# IMX385_PINOUT.net
KiCad netlist of a schematic drawn in Altium Designer
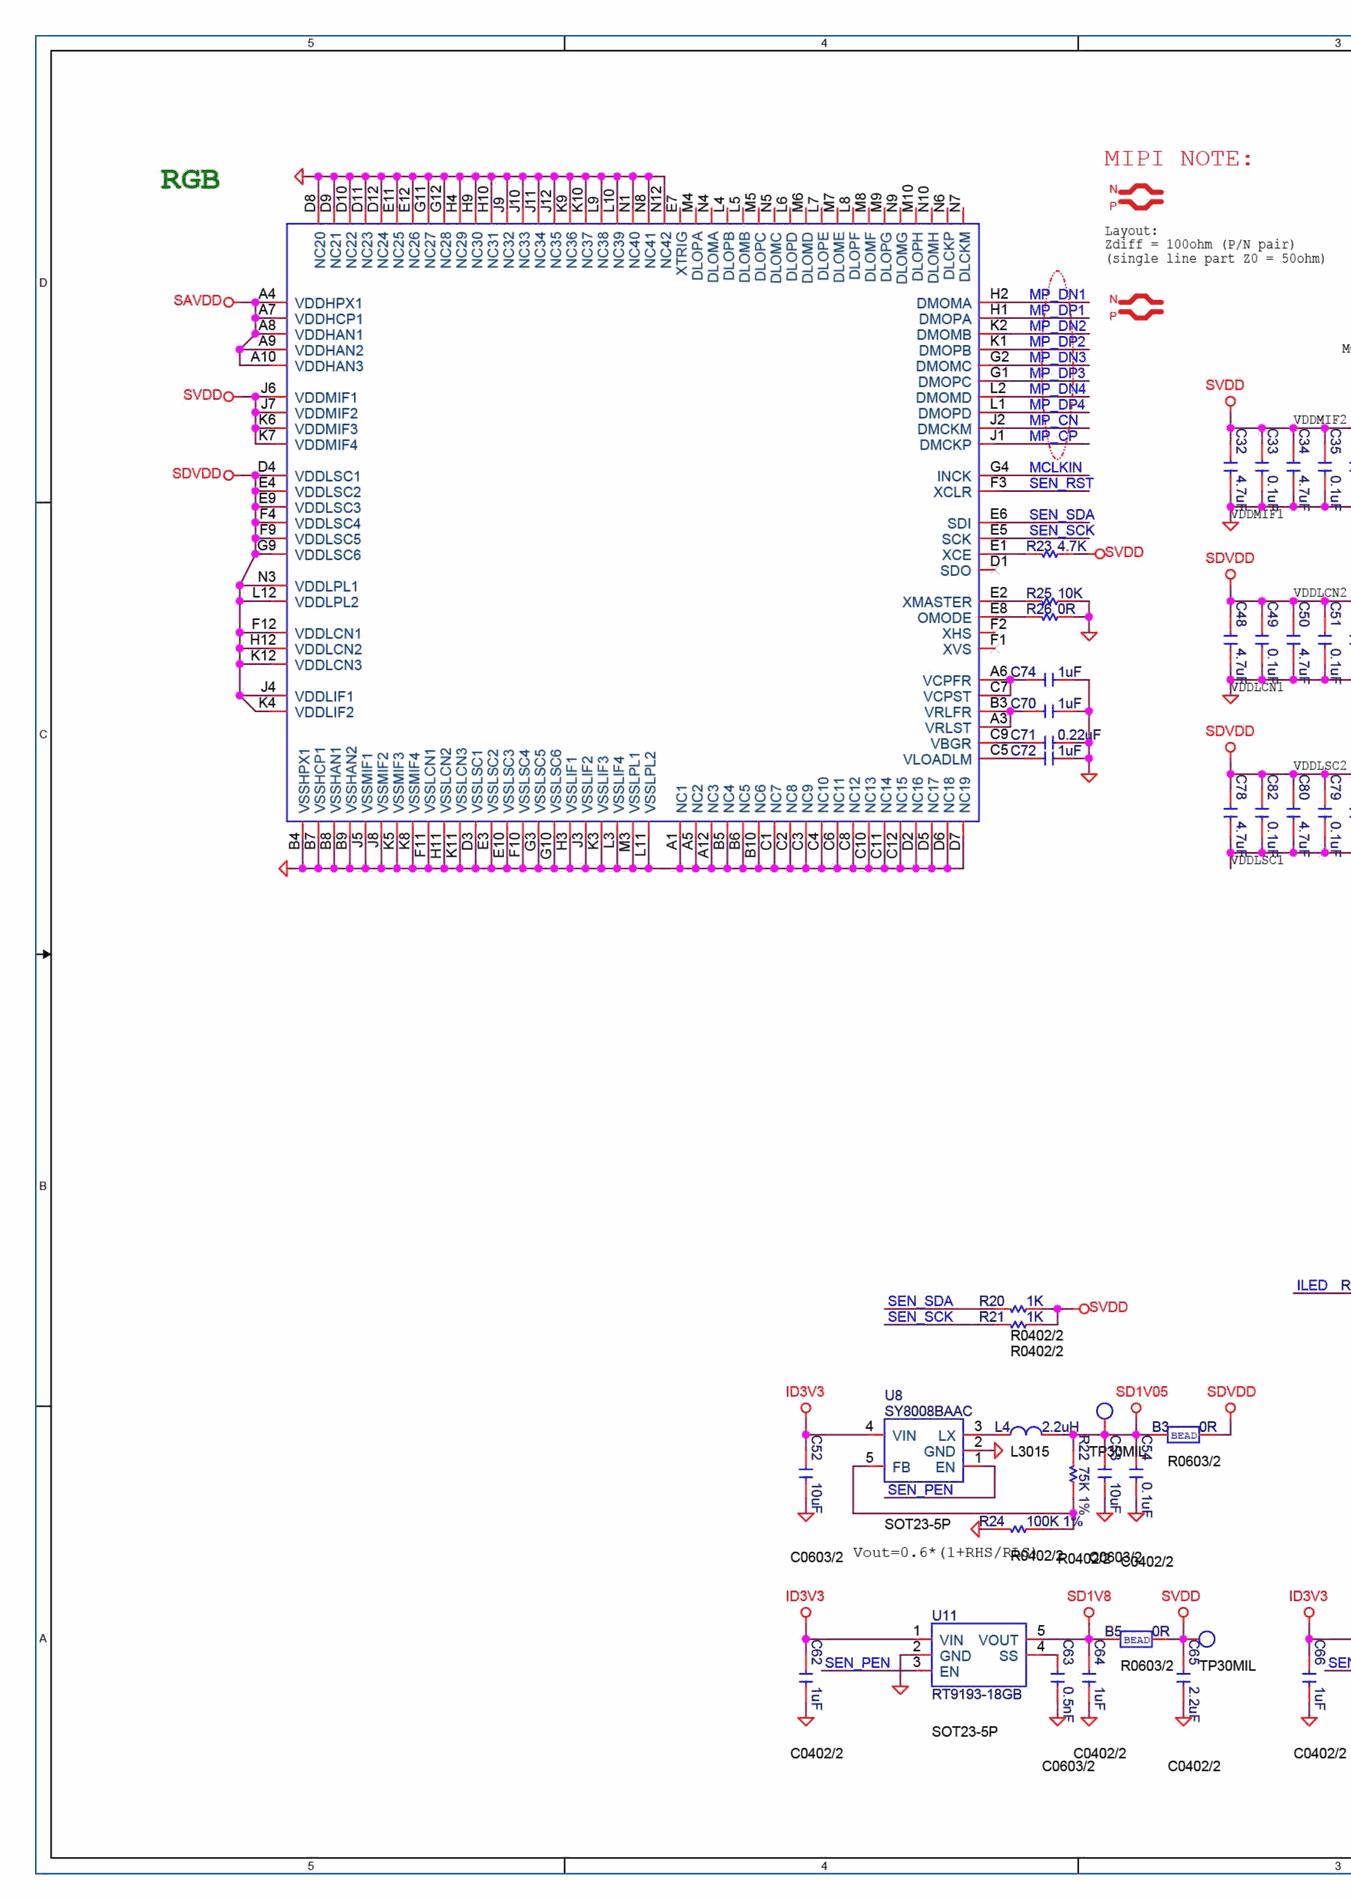
[diagram p0: IMX385_PINOUT.SchDoc, top left]
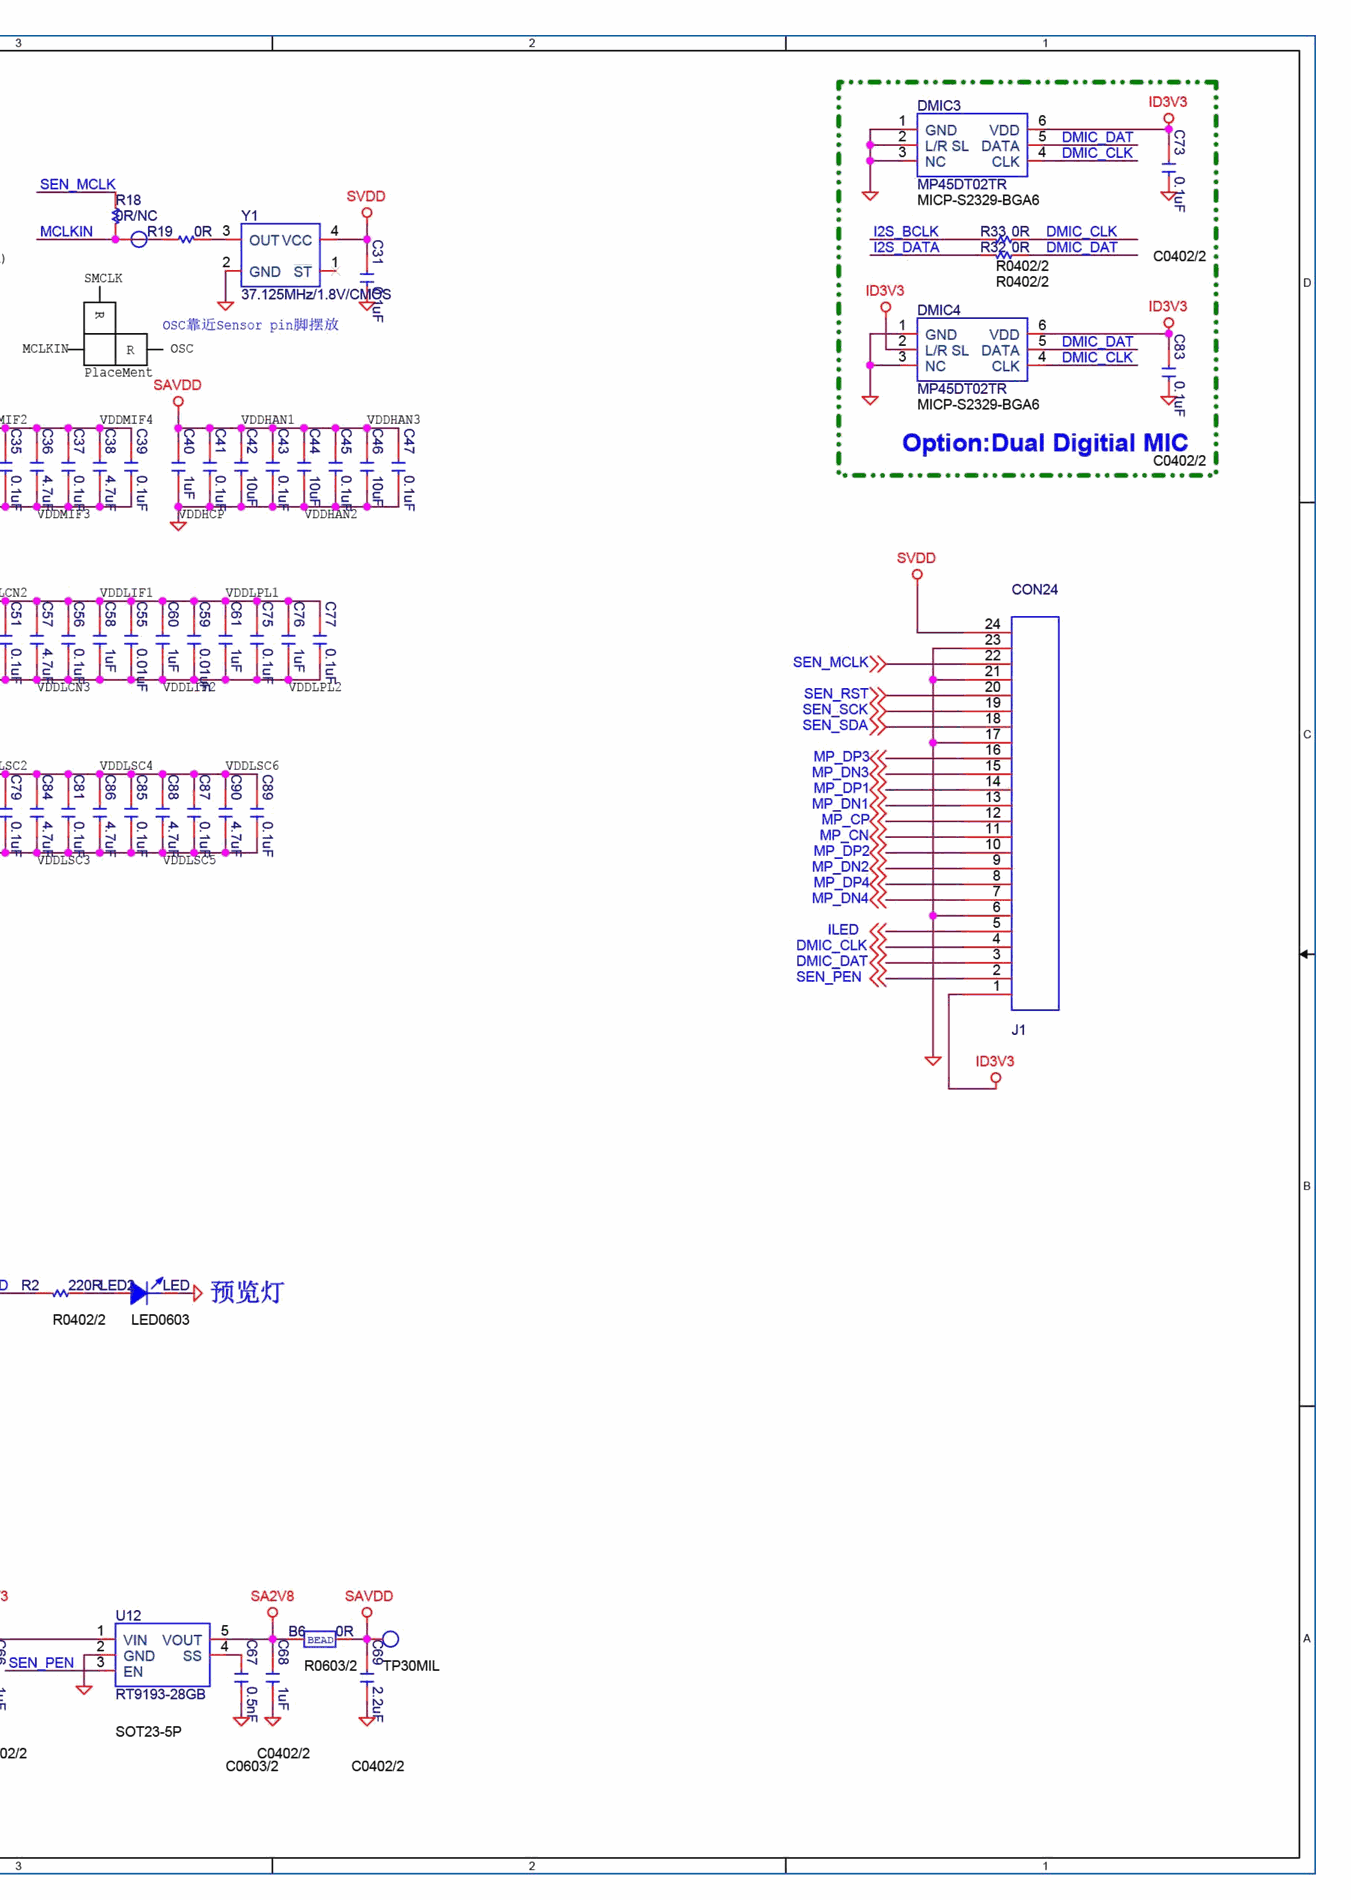
[diagram p1: IMX385_PINOUT.SchDoc, top right]
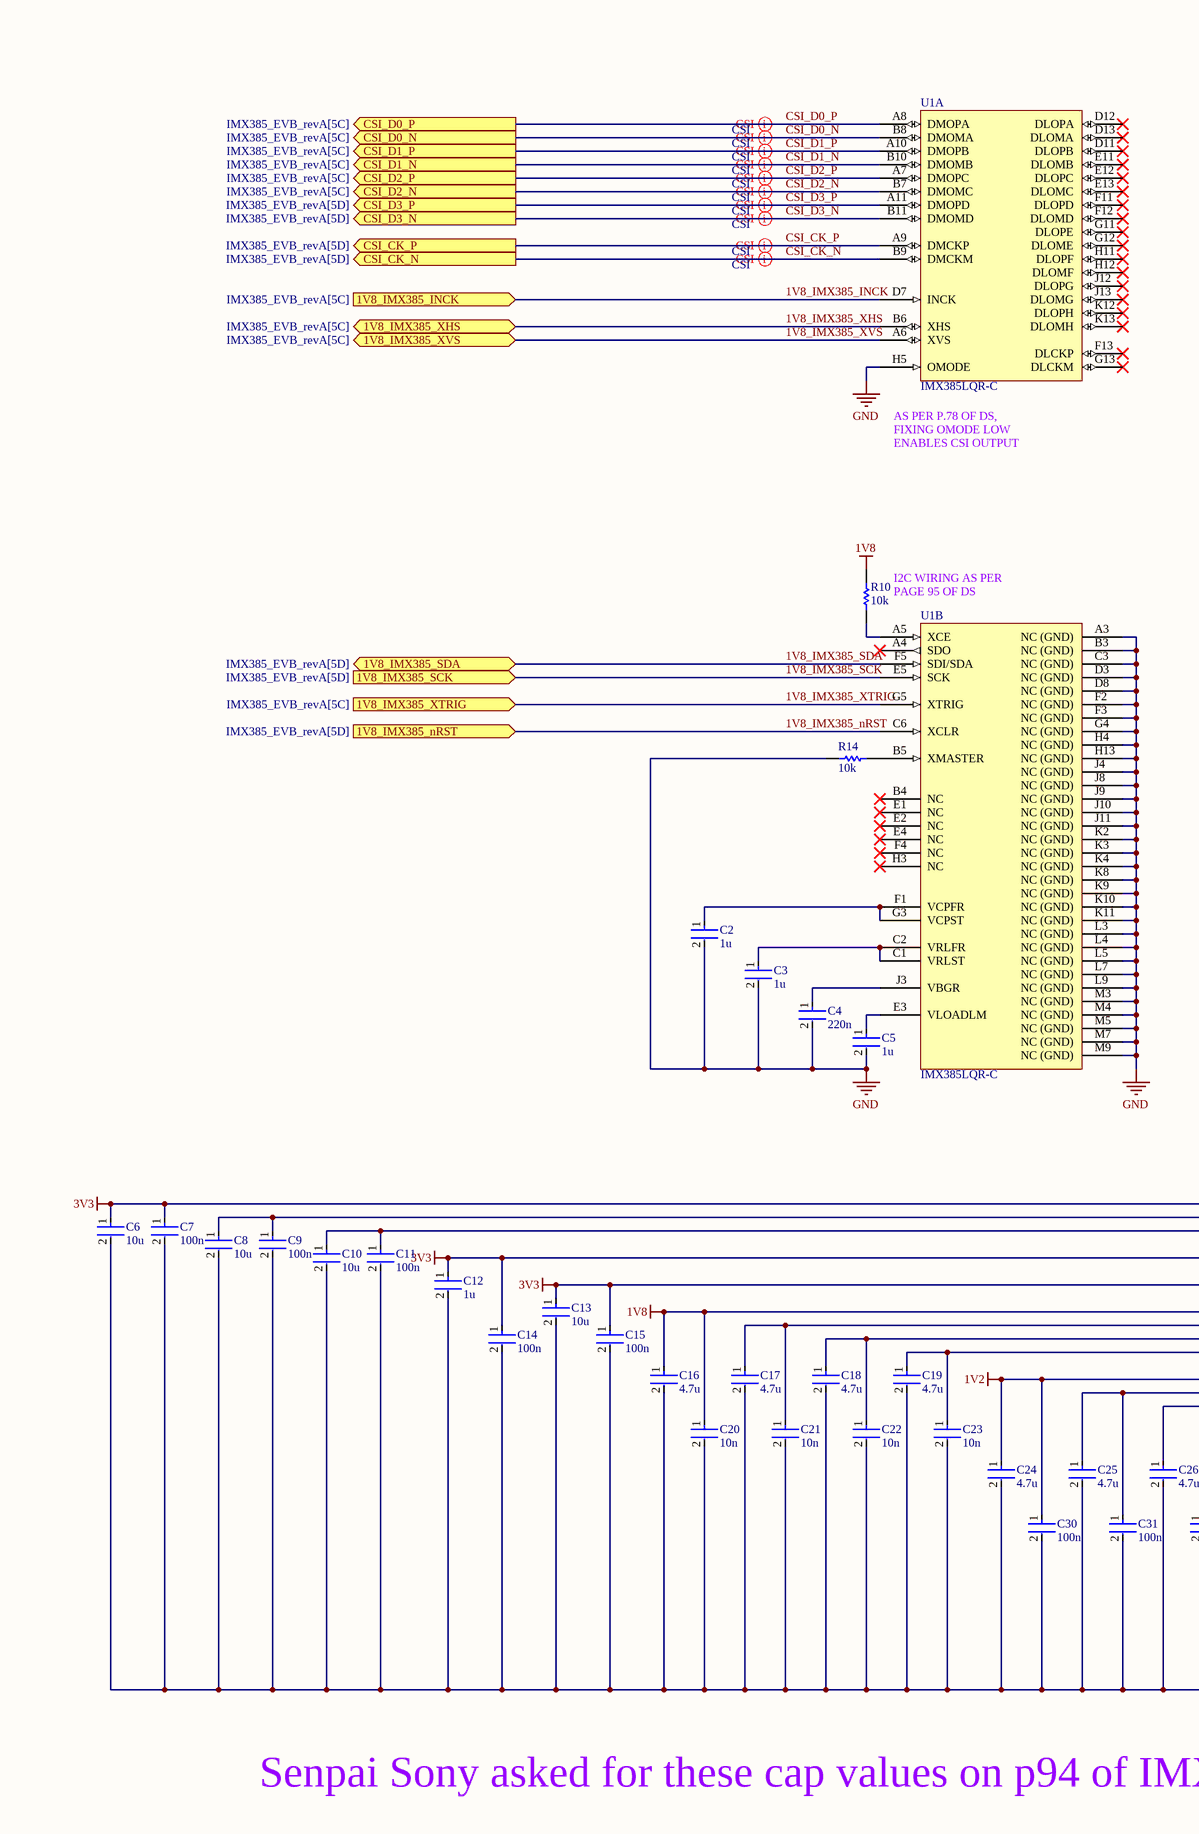
[diagram p2: IMX385_PINOUT.SchDoc, bottom left]
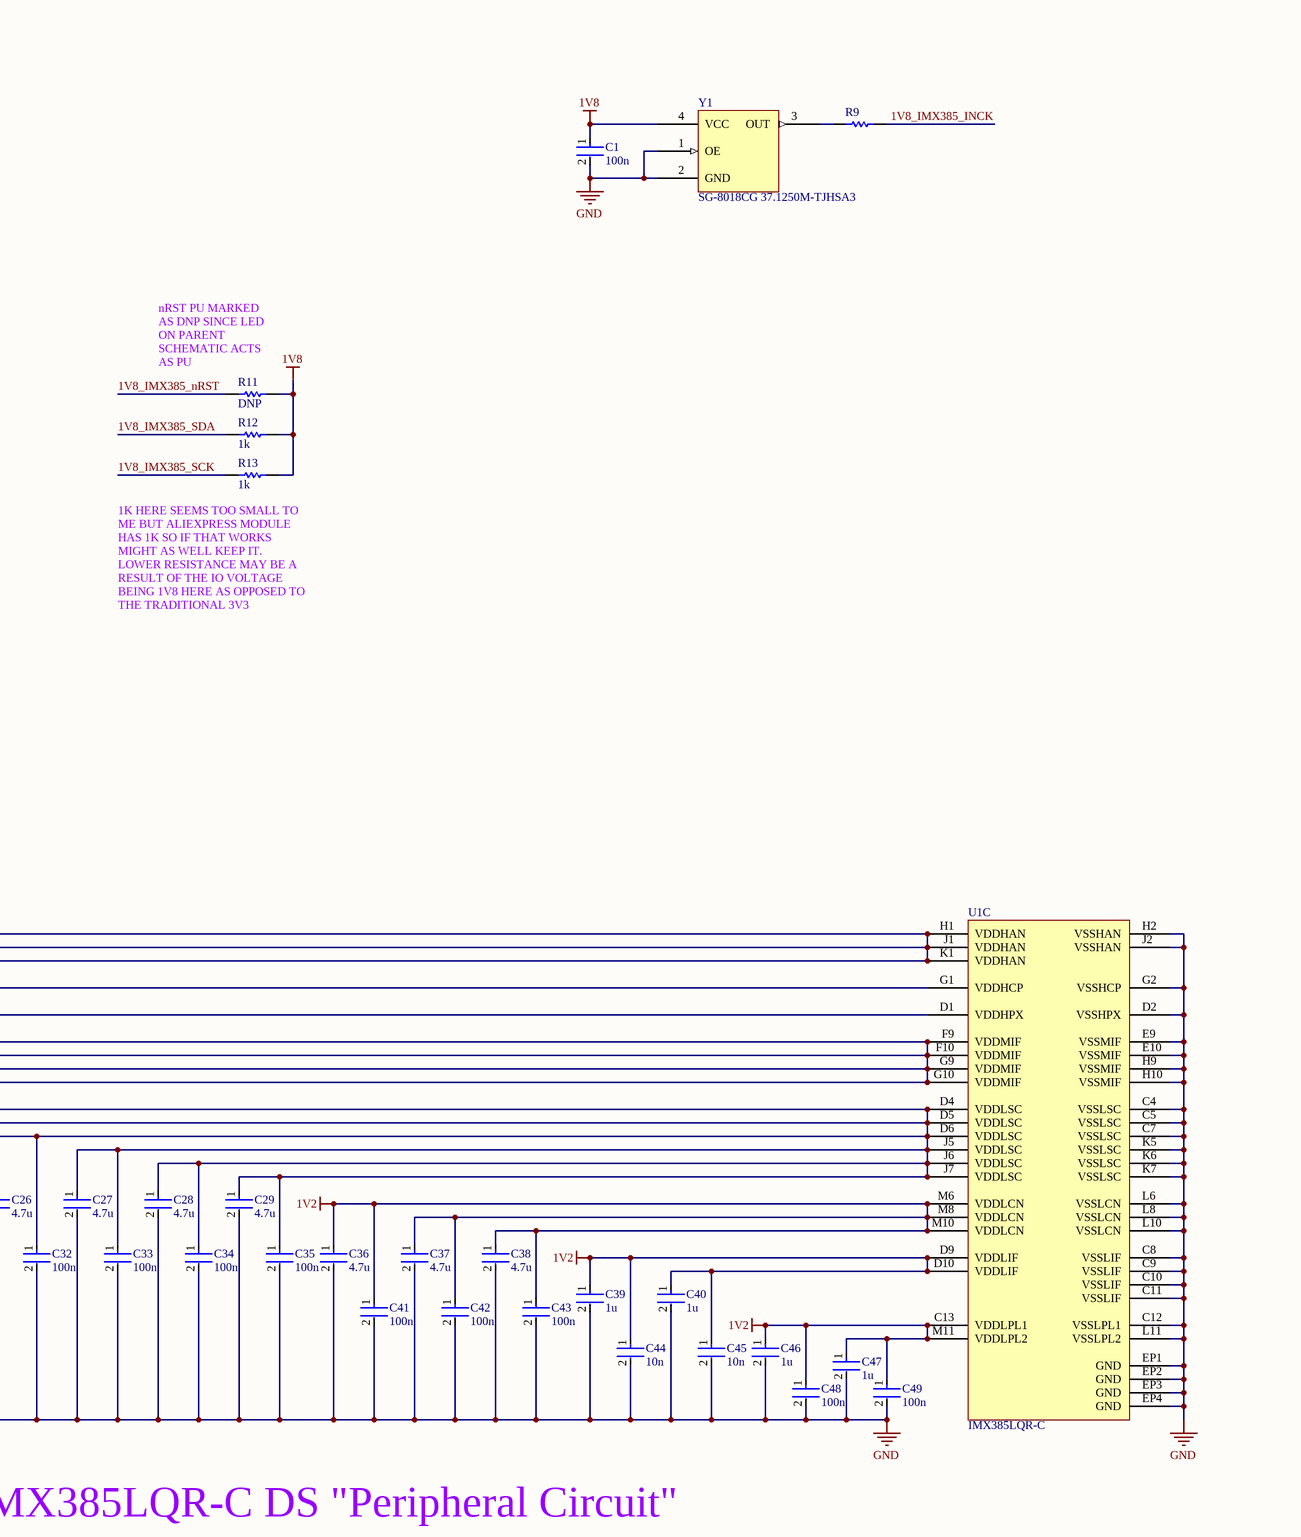
[diagram p3: IMX385_PINOUT.SchDoc, bottom right]

(export (version "E")
  (design (tool "Eeschema 10.0.6"))
  (components
    (comp (ref "C1")
      (value "100n")
      (footprint "FP-0402-L_1_0_0_05-W_0_5-IPC_A")
      (description "LARGE PADS, 0402 CAP, CHANGE COMMENT TO MATCH REAL P/N")
      (libsource (lib "Space Concordia") (part "b4654b650e69147ec39a6b967a45e02"))
    )
    (comp (ref "C2")
      (value "1u")
      (footprint "FP-0402-L_1_0_0_05-W_0_5-IPC_A")
      (description "LARGE PADS, 0402 CAP, CHANGE COMMENT TO MATCH REAL P/N")
      (libsource (lib "Space Concordia") (part "b4654b650e69147ec39a6b967a45e02"))
    )
    (comp (ref "C3")
      (value "1u")
      (footprint "FP-0402-L_1_0_0_05-W_0_5-IPC_A")
      (description "LARGE PADS, 0402 CAP, CHANGE COMMENT TO MATCH REAL P/N")
      (libsource (lib "Space Concordia") (part "b4654b650e69147ec39a6b967a45e02"))
    )
    (comp (ref "C4")
      (value "220n")
      (footprint "FP-0402-L_1_0_0_05-W_0_5-IPC_A")
      (description "LARGE PADS, 0402 CAP, CHANGE COMMENT TO MATCH REAL P/N")
      (libsource (lib "Space Concordia") (part "b4654b650e69147ec39a6b967a45e02"))
    )
    (comp (ref "C5")
      (value "1u")
      (footprint "FP-0402-L_1_0_0_05-W_0_5-IPC_A")
      (description "LARGE PADS, 0402 CAP, CHANGE COMMENT TO MATCH REAL P/N")
      (libsource (lib "Space Concordia") (part "b4654b650e69147ec39a6b967a45e02"))
    )
    (comp (ref "C6")
      (value "10u")
      (footprint "FP-0402-L_1_0_0_05-W_0_5-IPC_A")
      (description "LARGE PADS, 0402 CAP, CHANGE COMMENT TO MATCH REAL P/N")
      (libsource (lib "Space Concordia") (part "b4654b650e69147ec39a6b967a45e02"))
    )
    (comp (ref "C7")
      (value "100n")
      (footprint "FP-0402-L_1_0_0_05-W_0_5-IPC_A")
      (description "LARGE PADS, 0402 CAP, CHANGE COMMENT TO MATCH REAL P/N")
      (libsource (lib "Space Concordia") (part "b4654b650e69147ec39a6b967a45e02"))
    )
    (comp (ref "C8")
      (value "10u")
      (footprint "FP-0402-L_1_0_0_05-W_0_5-IPC_A")
      (description "LARGE PADS, 0402 CAP, CHANGE COMMENT TO MATCH REAL P/N")
      (libsource (lib "Space Concordia") (part "b4654b650e69147ec39a6b967a45e02"))
    )
    (comp (ref "C9")
      (value "100n")
      (footprint "FP-0402-L_1_0_0_05-W_0_5-IPC_A")
      (description "LARGE PADS, 0402 CAP, CHANGE COMMENT TO MATCH REAL P/N")
      (libsource (lib "Space Concordia") (part "b4654b650e69147ec39a6b967a45e02"))
    )
    (comp (ref "C10")
      (value "10u")
      (footprint "FP-0402-L_1_0_0_05-W_0_5-IPC_A")
      (description "LARGE PADS, 0402 CAP, CHANGE COMMENT TO MATCH REAL P/N")
      (libsource (lib "Space Concordia") (part "b4654b650e69147ec39a6b967a45e02"))
    )
    (comp (ref "C11")
      (value "100n")
      (footprint "FP-0402-L_1_0_0_05-W_0_5-IPC_A")
      (description "LARGE PADS, 0402 CAP, CHANGE COMMENT TO MATCH REAL P/N")
      (libsource (lib "Space Concordia") (part "b4654b650e69147ec39a6b967a45e02"))
    )
    (comp (ref "C12")
      (value "1u")
      (footprint "FP-0402-L_1_0_0_05-W_0_5-IPC_A")
      (description "LARGE PADS, 0402 CAP, CHANGE COMMENT TO MATCH REAL P/N")
      (libsource (lib "Space Concordia") (part "b4654b650e69147ec39a6b967a45e02"))
    )
    (comp (ref "C13")
      (value "10u")
      (footprint "FP-0402-L_1_0_0_05-W_0_5-IPC_A")
      (description "LARGE PADS, 0402 CAP, CHANGE COMMENT TO MATCH REAL P/N")
      (libsource (lib "Space Concordia") (part "b4654b650e69147ec39a6b967a45e02"))
    )
    (comp (ref "C14")
      (value "100n")
      (footprint "FP-0402-L_1_0_0_05-W_0_5-IPC_A")
      (description "LARGE PADS, 0402 CAP, CHANGE COMMENT TO MATCH REAL P/N")
      (libsource (lib "Space Concordia") (part "b4654b650e69147ec39a6b967a45e02"))
    )
    (comp (ref "C15")
      (value "100n")
      (footprint "FP-0402-L_1_0_0_05-W_0_5-IPC_A")
      (description "LARGE PADS, 0402 CAP, CHANGE COMMENT TO MATCH REAL P/N")
      (libsource (lib "Space Concordia") (part "b4654b650e69147ec39a6b967a45e02"))
    )
    (comp (ref "C16")
      (value "4.7u")
      (footprint "FP-0402-L_1_0_0_05-W_0_5-IPC_A")
      (description "LARGE PADS, 0402 CAP, CHANGE COMMENT TO MATCH REAL P/N")
      (libsource (lib "Space Concordia") (part "b4654b650e69147ec39a6b967a45e02"))
    )
    (comp (ref "C17")
      (value "4.7u")
      (footprint "FP-0402-L_1_0_0_05-W_0_5-IPC_A")
      (description "LARGE PADS, 0402 CAP, CHANGE COMMENT TO MATCH REAL P/N")
      (libsource (lib "Space Concordia") (part "b4654b650e69147ec39a6b967a45e02"))
    )
    (comp (ref "C18")
      (value "4.7u")
      (footprint "FP-0402-L_1_0_0_05-W_0_5-IPC_A")
      (description "LARGE PADS, 0402 CAP, CHANGE COMMENT TO MATCH REAL P/N")
      (libsource (lib "Space Concordia") (part "b4654b650e69147ec39a6b967a45e02"))
    )
    (comp (ref "C19")
      (value "4.7u")
      (footprint "FP-0402-L_1_0_0_05-W_0_5-IPC_A")
      (description "LARGE PADS, 0402 CAP, CHANGE COMMENT TO MATCH REAL P/N")
      (libsource (lib "Space Concordia") (part "b4654b650e69147ec39a6b967a45e02"))
    )
    (comp (ref "C20")
      (value "10n")
      (footprint "FP-0402-L_1_0_0_05-W_0_5-IPC_A")
      (description "LARGE PADS, 0402 CAP, CHANGE COMMENT TO MATCH REAL P/N")
      (libsource (lib "Space Concordia") (part "b4654b650e69147ec39a6b967a45e02"))
    )
    (comp (ref "C21")
      (value "10n")
      (footprint "FP-0402-L_1_0_0_05-W_0_5-IPC_A")
      (description "LARGE PADS, 0402 CAP, CHANGE COMMENT TO MATCH REAL P/N")
      (libsource (lib "Space Concordia") (part "b4654b650e69147ec39a6b967a45e02"))
    )
    (comp (ref "C22")
      (value "10n")
      (footprint "FP-0402-L_1_0_0_05-W_0_5-IPC_A")
      (description "LARGE PADS, 0402 CAP, CHANGE COMMENT TO MATCH REAL P/N")
      (libsource (lib "Space Concordia") (part "b4654b650e69147ec39a6b967a45e02"))
    )
    (comp (ref "C23")
      (value "10n")
      (footprint "FP-0402-L_1_0_0_05-W_0_5-IPC_A")
      (description "LARGE PADS, 0402 CAP, CHANGE COMMENT TO MATCH REAL P/N")
      (libsource (lib "Space Concordia") (part "b4654b650e69147ec39a6b967a45e02"))
    )
    (comp (ref "C24")
      (value "4.7u")
      (footprint "FP-0402-L_1_0_0_05-W_0_5-IPC_A")
      (description "LARGE PADS, 0402 CAP, CHANGE COMMENT TO MATCH REAL P/N")
      (libsource (lib "Space Concordia") (part "b4654b650e69147ec39a6b967a45e02"))
    )
    (comp (ref "C25")
      (value "4.7u")
      (footprint "FP-0402-L_1_0_0_05-W_0_5-IPC_A")
      (description "LARGE PADS, 0402 CAP, CHANGE COMMENT TO MATCH REAL P/N")
      (libsource (lib "Space Concordia") (part "b4654b650e69147ec39a6b967a45e02"))
    )
    (comp (ref "C26")
      (value "4.7u")
      (footprint "FP-0402-L_1_0_0_05-W_0_5-IPC_A")
      (description "LARGE PADS, 0402 CAP, CHANGE COMMENT TO MATCH REAL P/N")
      (libsource (lib "Space Concordia") (part "b4654b650e69147ec39a6b967a45e02"))
    )
    (comp (ref "C27")
      (value "4.7u")
      (footprint "FP-0402-L_1_0_0_05-W_0_5-IPC_A")
      (description "LARGE PADS, 0402 CAP, CHANGE COMMENT TO MATCH REAL P/N")
      (libsource (lib "Space Concordia") (part "b4654b650e69147ec39a6b967a45e02"))
    )
    (comp (ref "C28")
      (value "4.7u")
      (footprint "FP-0402-L_1_0_0_05-W_0_5-IPC_A")
      (description "LARGE PADS, 0402 CAP, CHANGE COMMENT TO MATCH REAL P/N")
      (libsource (lib "Space Concordia") (part "b4654b650e69147ec39a6b967a45e02"))
    )
    (comp (ref "C29")
      (value "4.7u")
      (footprint "FP-0402-L_1_0_0_05-W_0_5-IPC_A")
      (description "LARGE PADS, 0402 CAP, CHANGE COMMENT TO MATCH REAL P/N")
      (libsource (lib "Space Concordia") (part "b4654b650e69147ec39a6b967a45e02"))
    )
    (comp (ref "C30")
      (value "100n")
      (footprint "FP-0402-L_1_0_0_05-W_0_5-IPC_A")
      (description "LARGE PADS, 0402 CAP, CHANGE COMMENT TO MATCH REAL P/N")
      (libsource (lib "Space Concordia") (part "b4654b650e69147ec39a6b967a45e02"))
    )
    (comp (ref "C31")
      (value "100n")
      (footprint "FP-0402-L_1_0_0_05-W_0_5-IPC_A")
      (description "LARGE PADS, 0402 CAP, CHANGE COMMENT TO MATCH REAL P/N")
      (libsource (lib "Space Concordia") (part "b4654b650e69147ec39a6b967a45e02"))
    )
    (comp (ref "C32")
      (value "100n")
      (footprint "FP-0402-L_1_0_0_05-W_0_5-IPC_A")
      (description "LARGE PADS, 0402 CAP, CHANGE COMMENT TO MATCH REAL P/N")
      (libsource (lib "Space Concordia") (part "b4654b650e69147ec39a6b967a45e02"))
    )
    (comp (ref "C33")
      (value "100n")
      (footprint "FP-0402-L_1_0_0_05-W_0_5-IPC_A")
      (description "LARGE PADS, 0402 CAP, CHANGE COMMENT TO MATCH REAL P/N")
      (libsource (lib "Space Concordia") (part "b4654b650e69147ec39a6b967a45e02"))
    )
    (comp (ref "C34")
      (value "100n")
      (footprint "FP-0402-L_1_0_0_05-W_0_5-IPC_A")
      (description "LARGE PADS, 0402 CAP, CHANGE COMMENT TO MATCH REAL P/N")
      (libsource (lib "Space Concordia") (part "b4654b650e69147ec39a6b967a45e02"))
    )
    (comp (ref "C35")
      (value "100n")
      (footprint "FP-0402-L_1_0_0_05-W_0_5-IPC_A")
      (description "LARGE PADS, 0402 CAP, CHANGE COMMENT TO MATCH REAL P/N")
      (libsource (lib "Space Concordia") (part "b4654b650e69147ec39a6b967a45e02"))
    )
    (comp (ref "C36")
      (value "4.7u")
      (footprint "FP-0402-L_1_0_0_05-W_0_5-IPC_A")
      (description "LARGE PADS, 0402 CAP, CHANGE COMMENT TO MATCH REAL P/N")
      (libsource (lib "Space Concordia") (part "b4654b650e69147ec39a6b967a45e02"))
    )
    (comp (ref "C37")
      (value "4.7u")
      (footprint "FP-0402-L_1_0_0_05-W_0_5-IPC_A")
      (description "LARGE PADS, 0402 CAP, CHANGE COMMENT TO MATCH REAL P/N")
      (libsource (lib "Space Concordia") (part "b4654b650e69147ec39a6b967a45e02"))
    )
    (comp (ref "C38")
      (value "4.7u")
      (footprint "FP-0402-L_1_0_0_05-W_0_5-IPC_A")
      (description "LARGE PADS, 0402 CAP, CHANGE COMMENT TO MATCH REAL P/N")
      (libsource (lib "Space Concordia") (part "b4654b650e69147ec39a6b967a45e02"))
    )
    (comp (ref "C39")
      (value "1u")
      (footprint "FP-0402-L_1_0_0_05-W_0_5-IPC_A")
      (description "LARGE PADS, 0402 CAP, CHANGE COMMENT TO MATCH REAL P/N")
      (libsource (lib "Space Concordia") (part "b4654b650e69147ec39a6b967a45e02"))
    )
    (comp (ref "C40")
      (value "1u")
      (footprint "FP-0402-L_1_0_0_05-W_0_5-IPC_A")
      (description "LARGE PADS, 0402 CAP, CHANGE COMMENT TO MATCH REAL P/N")
      (libsource (lib "Space Concordia") (part "b4654b650e69147ec39a6b967a45e02"))
    )
    (comp (ref "C41")
      (value "100n")
      (footprint "FP-0402-L_1_0_0_05-W_0_5-IPC_A")
      (description "LARGE PADS, 0402 CAP, CHANGE COMMENT TO MATCH REAL P/N")
      (libsource (lib "Space Concordia") (part "b4654b650e69147ec39a6b967a45e02"))
    )
    (comp (ref "C42")
      (value "100n")
      (footprint "FP-0402-L_1_0_0_05-W_0_5-IPC_A")
      (description "LARGE PADS, 0402 CAP, CHANGE COMMENT TO MATCH REAL P/N")
      (libsource (lib "Space Concordia") (part "b4654b650e69147ec39a6b967a45e02"))
    )
    (comp (ref "C43")
      (value "100n")
      (footprint "FP-0402-L_1_0_0_05-W_0_5-IPC_A")
      (description "LARGE PADS, 0402 CAP, CHANGE COMMENT TO MATCH REAL P/N")
      (libsource (lib "Space Concordia") (part "b4654b650e69147ec39a6b967a45e02"))
    )
    (comp (ref "C44")
      (value "10n")
      (footprint "FP-0402-L_1_0_0_05-W_0_5-IPC_A")
      (description "LARGE PADS, 0402 CAP, CHANGE COMMENT TO MATCH REAL P/N")
      (libsource (lib "Space Concordia") (part "b4654b650e69147ec39a6b967a45e02"))
    )
    (comp (ref "C45")
      (value "10n")
      (footprint "FP-0402-L_1_0_0_05-W_0_5-IPC_A")
      (description "LARGE PADS, 0402 CAP, CHANGE COMMENT TO MATCH REAL P/N")
      (libsource (lib "Space Concordia") (part "b4654b650e69147ec39a6b967a45e02"))
    )
    (comp (ref "C46")
      (value "1u")
      (footprint "FP-0402-L_1_0_0_05-W_0_5-IPC_A")
      (description "LARGE PADS, 0402 CAP, CHANGE COMMENT TO MATCH REAL P/N")
      (libsource (lib "Space Concordia") (part "b4654b650e69147ec39a6b967a45e02"))
    )
    (comp (ref "C47")
      (value "1u")
      (footprint "FP-0402-L_1_0_0_05-W_0_5-IPC_A")
      (description "LARGE PADS, 0402 CAP, CHANGE COMMENT TO MATCH REAL P/N")
      (libsource (lib "Space Concordia") (part "b4654b650e69147ec39a6b967a45e02"))
    )
    (comp (ref "C48")
      (value "100n")
      (footprint "FP-0402-L_1_0_0_05-W_0_5-IPC_A")
      (description "LARGE PADS, 0402 CAP, CHANGE COMMENT TO MATCH REAL P/N")
      (libsource (lib "Space Concordia") (part "b4654b650e69147ec39a6b967a45e02"))
    )
    (comp (ref "C49")
      (value "100n")
      (footprint "FP-0402-L_1_0_0_05-W_0_5-IPC_A")
      (description "LARGE PADS, 0402 CAP, CHANGE COMMENT TO MATCH REAL P/N")
      (libsource (lib "Space Concordia") (part "b4654b650e69147ec39a6b967a45e02"))
    )
    (comp (ref "R9")
      (value "0402 JUMPER")
      (footprint "RESC1005X40X25ML05T05")
      (description "READ THE NAME")
      (libsource (lib "Space Concordia") (part "CMP-009-00206-2"))
    )
    (comp (ref "R10")
      (value "10k")
      (footprint "R0603B")
      (description "Resistor")
      (libsource (lib "Space Concordia") (part "Resistor"))
    )
    (comp (ref "R11")
      (value "DNP")
      (footprint "R0603B")
      (description "Resistor")
      (libsource (lib "Space Concordia") (part "Resistor"))
    )
    (comp (ref "R12")
      (value "1k")
      (footprint "R0603B")
      (description "Resistor")
      (libsource (lib "Space Concordia") (part "Resistor"))
    )
    (comp (ref "R13")
      (value "1k")
      (footprint "R0603B")
      (description "Resistor")
      (libsource (lib "Space Concordia") (part "Resistor"))
    )
    (comp (ref "R14")
      (value "10k")
      (footprint "R0603B")
      (description "Resistor")
      (libsource (lib "Space Concordia") (part "Resistor"))
    )
    (comp (ref "U1")
      (value "IMX385LQR-C")
      (footprint "BGA128C100P13X12_1500X1250X225")
      (description "Sony Starvis 2.13MP MIPI 1/2\" Image Sensor")
      (libsource (lib "Space Concordia") (part "IMX385LQR-C"))
    )
    (comp (ref "Y1")
      (value "SG-8018CG 37.1250M-TJHSA3")
      (footprint "SG-8018CG 37.1250M-TJHSA3-Footprint-1")
      (description "SG-8018CG 37.1250M-TJHSA3: Mhz Osc 1.8V~3.3V +/-50PPM -40~105C St 250TR")
      (libsource (lib "Space Concordia") (part "SG-8018CG 37.1250M-TJHSA3"))
    )
  )
  (nets
    (net (code "1") (name "/1V8_IMX385_INCK") (class "Default")
      (node (ref "R9") (pin "2") (pinfunction "2_2") (pintype "passive"))
      (node (ref "U1") (pin "D7") (pinfunction "INCK_D7") (pintype "input"))
    )
    (net (code "2") (name "/1V8_IMX385_SCK") (class "Default")
      (node (ref "R13") (pin "1") (pinfunction "1_1") (pintype "passive"))
      (node (ref "U1") (pin "E5") (pinfunction "SCK_E5") (pintype "input"))
    )
    (net (code "3") (name "/1V8_IMX385_SDA") (class "Default")
      (node (ref "R12") (pin "1") (pinfunction "1_1") (pintype "passive"))
      (node (ref "U1") (pin "F5") (pinfunction "SDI/SDA_F5") (pintype "input"))
    )
    (net (code "4") (name "/1V8_IMX385_XHS") (class "Default")
      (node (ref "U1") (pin "B6") (pinfunction "XHS_B6") (pintype "bidirectional"))
    )
    (net (code "5") (name "/1V8_IMX385_XTRIG") (class "Default")
      (node (ref "U1") (pin "G5") (pinfunction "XTRIG_G5") (pintype "input"))
    )
    (net (code "6") (name "/1V8_IMX385_XVS") (class "Default")
      (node (ref "U1") (pin "A6") (pinfunction "XVS_A6") (pintype "bidirectional"))
    )
    (net (code "7") (name "/1V8_IMX385_nRST") (class "Default")
      (node (ref "R11") (pin "2") (pinfunction "2_2") (pintype "passive"))
      (node (ref "U1") (pin "C6") (pinfunction "XCLR_C6") (pintype "input"))
    )
    (net (code "8") (name "/CSI_CK_N") (class "Default")
      (node (ref "U1") (pin "B9") (pinfunction "DMCKM_B9") (pintype "bidirectional"))
    )
    (net (code "9") (name "/CSI_CK_P") (class "Default")
      (node (ref "U1") (pin "A9") (pinfunction "DMCKP_A9") (pintype "bidirectional"))
    )
    (net (code "10") (name "/CSI_D0_N") (class "Default")
      (node (ref "U1") (pin "B8") (pinfunction "DMOMA_B8") (pintype "bidirectional"))
    )
    (net (code "11") (name "/CSI_D0_P") (class "Default")
      (node (ref "U1") (pin "A8") (pinfunction "DMOPA_A8") (pintype "bidirectional"))
    )
    (net (code "12") (name "/CSI_D1_N") (class "Default")
      (node (ref "U1") (pin "B10") (pinfunction "DMOMB_B10") (pintype "bidirectional"))
    )
    (net (code "13") (name "/CSI_D1_P") (class "Default")
      (node (ref "U1") (pin "A10") (pinfunction "DMOPB_A10") (pintype "bidirectional"))
    )
    (net (code "14") (name "/CSI_D2_N") (class "Default")
      (node (ref "U1") (pin "B7") (pinfunction "DMOMC_B7") (pintype "bidirectional"))
    )
    (net (code "15") (name "/CSI_D2_P") (class "Default")
      (node (ref "U1") (pin "A7") (pinfunction "DMOPC_A7") (pintype "bidirectional"))
    )
    (net (code "16") (name "/CSI_D3_N") (class "Default")
      (node (ref "U1") (pin "B11") (pinfunction "DMOMD_B11") (pintype "bidirectional"))
    )
    (net (code "17") (name "/CSI_D3_P") (class "Default")
      (node (ref "U1") (pin "A11") (pinfunction "DMOPD_A11") (pintype "bidirectional"))
    )
    (net (code "18") (name "1V2") (class "Default")
      (node (ref "C24") (pin "1") (pinfunction "1_1") (pintype "passive"))
      (node (ref "C25") (pin "1") (pinfunction "1_1") (pintype "passive"))
      (node (ref "C26") (pin "1") (pinfunction "1_1") (pintype "passive"))
      (node (ref "C27") (pin "1") (pinfunction "1_1") (pintype "passive"))
      (node (ref "C28") (pin "1") (pinfunction "1_1") (pintype "passive"))
      (node (ref "C29") (pin "1") (pinfunction "1_1") (pintype "passive"))
      (node (ref "C30") (pin "1") (pinfunction "1_1") (pintype "passive"))
      (node (ref "C31") (pin "1") (pinfunction "1_1") (pintype "passive"))
      (node (ref "C32") (pin "1") (pinfunction "1_1") (pintype "passive"))
      (node (ref "C33") (pin "1") (pinfunction "1_1") (pintype "passive"))
      (node (ref "C34") (pin "1") (pinfunction "1_1") (pintype "passive"))
      (node (ref "C35") (pin "1") (pinfunction "1_1") (pintype "passive"))
      (node (ref "C36") (pin "1") (pinfunction "1_1") (pintype "passive"))
      (node (ref "C37") (pin "1") (pinfunction "1_1") (pintype "passive"))
      (node (ref "C38") (pin "1") (pinfunction "1_1") (pintype "passive"))
      (node (ref "C39") (pin "1") (pinfunction "1_1") (pintype "passive"))
      (node (ref "C40") (pin "1") (pinfunction "1_1") (pintype "passive"))
      (node (ref "C41") (pin "1") (pinfunction "1_1") (pintype "passive"))
      (node (ref "C42") (pin "1") (pinfunction "1_1") (pintype "passive"))
      (node (ref "C43") (pin "1") (pinfunction "1_1") (pintype "passive"))
      (node (ref "C44") (pin "1") (pinfunction "1_1") (pintype "passive"))
      (node (ref "C45") (pin "1") (pinfunction "1_1") (pintype "passive"))
      (node (ref "C46") (pin "1") (pinfunction "1_1") (pintype "passive"))
      (node (ref "C47") (pin "1") (pinfunction "1_1") (pintype "passive"))
      (node (ref "C48") (pin "1") (pinfunction "1_1") (pintype "passive"))
      (node (ref "C49") (pin "1") (pinfunction "1_1") (pintype "passive"))
      (node (ref "U1") (pin "C13") (pinfunction "VDDLPL1_C13") (pintype "power_in"))
      (node (ref "U1") (pin "D10") (pinfunction "VDDLIF_D10") (pintype "power_in"))
      (node (ref "U1") (pin "D4") (pinfunction "VDDLSC_D4") (pintype "power_in"))
      (node (ref "U1") (pin "D5") (pinfunction "VDDLSC_D5") (pintype "power_in"))
      (node (ref "U1") (pin "D6") (pinfunction "VDDLSC_D6") (pintype "power_in"))
      (node (ref "U1") (pin "D9") (pinfunction "VDDLIF_D9") (pintype "power_in"))
      (node (ref "U1") (pin "J5") (pinfunction "VDDLSC_J5") (pintype "power_in"))
      (node (ref "U1") (pin "J6") (pinfunction "VDDLSC_J6") (pintype "power_in"))
      (node (ref "U1") (pin "J7") (pinfunction "VDDLSC_J7") (pintype "power_in"))
      (node (ref "U1") (pin "M10") (pinfunction "VDDLCN_M10") (pintype "power_in"))
      (node (ref "U1") (pin "M11") (pinfunction "VDDLPL2_M11") (pintype "power_in"))
      (node (ref "U1") (pin "M6") (pinfunction "VDDLCN_M6") (pintype "power_in"))
      (node (ref "U1") (pin "M8") (pinfunction "VDDLCN_M8") (pintype "power_in"))
    )
    (net (code "19") (name "1V8") (class "Default")
      (node (ref "C1") (pin "1") (pinfunction "1_1") (pintype "passive"))
      (node (ref "C16") (pin "1") (pinfunction "1_1") (pintype "passive"))
      (node (ref "C17") (pin "1") (pinfunction "1_1") (pintype "passive"))
      (node (ref "C18") (pin "1") (pinfunction "1_1") (pintype "passive"))
      (node (ref "C19") (pin "1") (pinfunction "1_1") (pintype "passive"))
      (node (ref "C20") (pin "1") (pinfunction "1_1") (pintype "passive"))
      (node (ref "C21") (pin "1") (pinfunction "1_1") (pintype "passive"))
      (node (ref "C22") (pin "1") (pinfunction "1_1") (pintype "passive"))
      (node (ref "C23") (pin "1") (pinfunction "1_1") (pintype "passive"))
      (node (ref "R10") (pin "2") (pinfunction "2_2") (pintype "passive"))
      (node (ref "R11") (pin "1") (pinfunction "1_1") (pintype "passive"))
      (node (ref "R12") (pin "2") (pinfunction "2_2") (pintype "passive"))
      (node (ref "R13") (pin "2") (pinfunction "2_2") (pintype "passive"))
      (node (ref "U1") (pin "F10") (pinfunction "VDDMIF_F10") (pintype "power_in"))
      (node (ref "U1") (pin "F9") (pinfunction "VDDMIF_F9") (pintype "power_in"))
      (node (ref "U1") (pin "G10") (pinfunction "VDDMIF_G10") (pintype "power_in"))
      (node (ref "U1") (pin "G9") (pinfunction "VDDMIF_G9") (pintype "power_in"))
      (node (ref "Y1") (pin "4") (pinfunction "VCC_4") (pintype "power_in"))
    )
    (net (code "20") (name "3V3") (class "Default")
      (node (ref "C10") (pin "1") (pinfunction "1_1") (pintype "passive"))
      (node (ref "C11") (pin "1") (pinfunction "1_1") (pintype "passive"))
      (node (ref "C12") (pin "1") (pinfunction "1_1") (pintype "passive"))
      (node (ref "C13") (pin "1") (pinfunction "1_1") (pintype "passive"))
      (node (ref "C14") (pin "1") (pinfunction "1_1") (pintype "passive"))
      (node (ref "C15") (pin "1") (pinfunction "1_1") (pintype "passive"))
      (node (ref "C6") (pin "1") (pinfunction "1_1") (pintype "passive"))
      (node (ref "C7") (pin "1") (pinfunction "1_1") (pintype "passive"))
      (node (ref "C8") (pin "1") (pinfunction "1_1") (pintype "passive"))
      (node (ref "C9") (pin "1") (pinfunction "1_1") (pintype "passive"))
      (node (ref "U1") (pin "D1") (pinfunction "VDDHPX_D1") (pintype "power_in"))
      (node (ref "U1") (pin "G1") (pinfunction "VDDHCP_G1") (pintype "power_in"))
      (node (ref "U1") (pin "H1") (pinfunction "VDDHAN_H1") (pintype "power_in"))
      (node (ref "U1") (pin "J1") (pinfunction "VDDHAN_J1") (pintype "power_in"))
      (node (ref "U1") (pin "K1") (pinfunction "VDDHAN_K1") (pintype "power_in"))
    )
    (net (code "21") (name "GND") (class "Default")
      (node (ref "C1") (pin "2") (pinfunction "2_2") (pintype "passive"))
      (node (ref "C10") (pin "2") (pinfunction "2_2") (pintype "passive"))
      (node (ref "C11") (pin "2") (pinfunction "2_2") (pintype "passive"))
      (node (ref "C12") (pin "2") (pinfunction "2_2") (pintype "passive"))
      (node (ref "C13") (pin "2") (pinfunction "2_2") (pintype "passive"))
      (node (ref "C14") (pin "2") (pinfunction "2_2") (pintype "passive"))
      (node (ref "C15") (pin "2") (pinfunction "2_2") (pintype "passive"))
      (node (ref "C16") (pin "2") (pinfunction "2_2") (pintype "passive"))
      (node (ref "C17") (pin "2") (pinfunction "2_2") (pintype "passive"))
      (node (ref "C18") (pin "2") (pinfunction "2_2") (pintype "passive"))
      (node (ref "C19") (pin "2") (pinfunction "2_2") (pintype "passive"))
      (node (ref "C2") (pin "2") (pinfunction "2_2") (pintype "passive"))
      (node (ref "C20") (pin "2") (pinfunction "2_2") (pintype "passive"))
      (node (ref "C21") (pin "2") (pinfunction "2_2") (pintype "passive"))
      (node (ref "C22") (pin "2") (pinfunction "2_2") (pintype "passive"))
      (node (ref "C23") (pin "2") (pinfunction "2_2") (pintype "passive"))
      (node (ref "C24") (pin "2") (pinfunction "2_2") (pintype "passive"))
      (node (ref "C25") (pin "2") (pinfunction "2_2") (pintype "passive"))
      (node (ref "C26") (pin "2") (pinfunction "2_2") (pintype "passive"))
      (node (ref "C27") (pin "2") (pinfunction "2_2") (pintype "passive"))
      (node (ref "C28") (pin "2") (pinfunction "2_2") (pintype "passive"))
      (node (ref "C29") (pin "2") (pinfunction "2_2") (pintype "passive"))
      (node (ref "C3") (pin "2") (pinfunction "2_2") (pintype "passive"))
      (node (ref "C30") (pin "2") (pinfunction "2_2") (pintype "passive"))
      (node (ref "C31") (pin "2") (pinfunction "2_2") (pintype "passive"))
      (node (ref "C32") (pin "2") (pinfunction "2_2") (pintype "passive"))
      (node (ref "C33") (pin "2") (pinfunction "2_2") (pintype "passive"))
      (node (ref "C34") (pin "2") (pinfunction "2_2") (pintype "passive"))
      (node (ref "C35") (pin "2") (pinfunction "2_2") (pintype "passive"))
      (node (ref "C36") (pin "2") (pinfunction "2_2") (pintype "passive"))
      (node (ref "C37") (pin "2") (pinfunction "2_2") (pintype "passive"))
      (node (ref "C38") (pin "2") (pinfunction "2_2") (pintype "passive"))
      (node (ref "C39") (pin "2") (pinfunction "2_2") (pintype "passive"))
      (node (ref "C4") (pin "2") (pinfunction "2_2") (pintype "passive"))
      (node (ref "C40") (pin "2") (pinfunction "2_2") (pintype "passive"))
      (node (ref "C41") (pin "2") (pinfunction "2_2") (pintype "passive"))
      (node (ref "C42") (pin "2") (pinfunction "2_2") (pintype "passive"))
      (node (ref "C43") (pin "2") (pinfunction "2_2") (pintype "passive"))
      (node (ref "C44") (pin "2") (pinfunction "2_2") (pintype "passive"))
      (node (ref "C45") (pin "2") (pinfunction "2_2") (pintype "passive"))
      (node (ref "C46") (pin "2") (pinfunction "2_2") (pintype "passive"))
      (node (ref "C47") (pin "2") (pinfunction "2_2") (pintype "passive"))
      (node (ref "C48") (pin "2") (pinfunction "2_2") (pintype "passive"))
      (node (ref "C49") (pin "2") (pinfunction "2_2") (pintype "passive"))
      (node (ref "C5") (pin "2") (pinfunction "2_2") (pintype "passive"))
      (node (ref "C6") (pin "2") (pinfunction "2_2") (pintype "passive"))
      (node (ref "C7") (pin "2") (pinfunction "2_2") (pintype "passive"))
      (node (ref "C8") (pin "2") (pinfunction "2_2") (pintype "passive"))
      (node (ref "C9") (pin "2") (pinfunction "2_2") (pintype "passive"))
      (node (ref "R14") (pin "2") (pinfunction "2_2") (pintype "passive"))
      (node (ref "U1") (pin "A3") (pinfunction "NC_(GND)_A3") (pintype "passive"))
      (node (ref "U1") (pin "B3") (pinfunction "NC_(GND)_B3") (pintype "passive"))
      (node (ref "U1") (pin "C10") (pinfunction "VSSLIF_C10") (pintype "power_in"))
      (node (ref "U1") (pin "C11") (pinfunction "VSSLIF_C11") (pintype "power_in"))
      (node (ref "U1") (pin "C12") (pinfunction "VSSLPL1_C12") (pintype "power_in"))
      (node (ref "U1") (pin "C3") (pinfunction "NC_(GND)_C3") (pintype "passive"))
      (node (ref "U1") (pin "C4") (pinfunction "VSSLSC_C4") (pintype "power_in"))
      (node (ref "U1") (pin "C5") (pinfunction "VSSLSC_C5") (pintype "power_in"))
      (node (ref "U1") (pin "C7") (pinfunction "VSSLSC_C7") (pintype "power_in"))
      (node (ref "U1") (pin "C8") (pinfunction "VSSLIF_C8") (pintype "power_in"))
      (node (ref "U1") (pin "C9") (pinfunction "VSSLIF_C9") (pintype "power_in"))
      (node (ref "U1") (pin "D2") (pinfunction "VSSHPX_D2") (pintype "power_in"))
      (node (ref "U1") (pin "D3") (pinfunction "NC_(GND)_D3") (pintype "passive"))
      (node (ref "U1") (pin "D8") (pinfunction "NC_(GND)_D8") (pintype "passive"))
      (node (ref "U1") (pin "E10") (pinfunction "VSSMIF_E10") (pintype "power_in"))
      (node (ref "U1") (pin "E9") (pinfunction "VSSMIF_E9") (pintype "power_in"))
      (node (ref "U1") (pin "EP1") (pinfunction "GND_EP1") (pintype "power_in"))
      (node (ref "U1") (pin "EP2") (pinfunction "GND_EP2") (pintype "power_in"))
      (node (ref "U1") (pin "EP3") (pinfunction "GND_EP3") (pintype "power_in"))
      (node (ref "U1") (pin "EP4") (pinfunction "GND_EP4") (pintype "power_in"))
      (node (ref "U1") (pin "F2") (pinfunction "NC_(GND)_F2") (pintype "passive"))
      (node (ref "U1") (pin "F3") (pinfunction "NC_(GND)_F3") (pintype "passive"))
      (node (ref "U1") (pin "G2") (pinfunction "VSSHCP_G2") (pintype "power_in"))
      (node (ref "U1") (pin "G4") (pinfunction "NC_(GND)_G4") (pintype "passive"))
      (node (ref "U1") (pin "H10") (pinfunction "VSSMIF_H10") (pintype "power_in"))
      (node (ref "U1") (pin "H13") (pinfunction "NC_(GND)_H13") (pintype "passive"))
      (node (ref "U1") (pin "H2") (pinfunction "VSSHAN_H2") (pintype "power_in"))
      (node (ref "U1") (pin "H4") (pinfunction "NC_(GND)_H4") (pintype "passive"))
      (node (ref "U1") (pin "H5") (pinfunction "OMODE_H5") (pintype "input"))
      (node (ref "U1") (pin "H9") (pinfunction "VSSMIF_H9") (pintype "power_in"))
      (node (ref "U1") (pin "J10") (pinfunction "NC_(GND)_J10") (pintype "passive"))
      (node (ref "U1") (pin "J11") (pinfunction "NC_(GND)_J11") (pintype "passive"))
      (node (ref "U1") (pin "J2") (pinfunction "VSSHAN_J2") (pintype "power_in"))
      (node (ref "U1") (pin "J4") (pinfunction "NC_(GND)_J4") (pintype "passive"))
      (node (ref "U1") (pin "J8") (pinfunction "NC_(GND)_J8") (pintype "passive"))
      (node (ref "U1") (pin "J9") (pinfunction "NC_(GND)_J9") (pintype "passive"))
      (node (ref "U1") (pin "K10") (pinfunction "NC_(GND)_K10") (pintype "passive"))
      (node (ref "U1") (pin "K11") (pinfunction "NC_(GND)_K11") (pintype "passive"))
      (node (ref "U1") (pin "K2") (pinfunction "NC_(GND)_K2") (pintype "passive"))
      (node (ref "U1") (pin "K3") (pinfunction "NC_(GND)_K3") (pintype "passive"))
      (node (ref "U1") (pin "K4") (pinfunction "NC_(GND)_K4") (pintype "passive"))
      (node (ref "U1") (pin "K5") (pinfunction "VSSLSC_K5") (pintype "power_in"))
      (node (ref "U1") (pin "K6") (pinfunction "VSSLSC_K6") (pintype "power_in"))
      (node (ref "U1") (pin "K7") (pinfunction "VSSLSC_K7") (pintype "power_in"))
      (node (ref "U1") (pin "K8") (pinfunction "NC_(GND)_K8") (pintype "passive"))
      (node (ref "U1") (pin "K9") (pinfunction "NC_(GND)_K9") (pintype "passive"))
      (node (ref "U1") (pin "L10") (pinfunction "VSSLCN_L10") (pintype "power_in"))
      (node (ref "U1") (pin "L11") (pinfunction "VSSLPL2_L11") (pintype "power_in"))
      (node (ref "U1") (pin "L3") (pinfunction "NC_(GND)_L3") (pintype "passive"))
      (node (ref "U1") (pin "L4") (pinfunction "NC_(GND)_L4") (pintype "passive"))
      (node (ref "U1") (pin "L5") (pinfunction "NC_(GND)_L5") (pintype "passive"))
      (node (ref "U1") (pin "L6") (pinfunction "VSSLCN_L6") (pintype "power_in"))
      (node (ref "U1") (pin "L7") (pinfunction "NC_(GND)_L7") (pintype "passive"))
      (node (ref "U1") (pin "L8") (pinfunction "VSSLCN_L8") (pintype "power_in"))
      (node (ref "U1") (pin "L9") (pinfunction "NC_(GND)_L9") (pintype "passive"))
      (node (ref "U1") (pin "M3") (pinfunction "NC_(GND)_M3") (pintype "passive"))
      (node (ref "U1") (pin "M4") (pinfunction "NC_(GND)_M4") (pintype "passive"))
      (node (ref "U1") (pin "M5") (pinfunction "NC_(GND)_M5") (pintype "passive"))
      (node (ref "U1") (pin "M7") (pinfunction "NC_(GND)_M7") (pintype "passive"))
      (node (ref "U1") (pin "M9") (pinfunction "NC_(GND)_M9") (pintype "passive"))
      (node (ref "Y1") (pin "1") (pinfunction "OE_1") (pintype "input"))
      (node (ref "Y1") (pin "2") (pinfunction "GND_2") (pintype "power_in"))
    )
    (net (code "22") (name "Net-(U1B-VBGR)") (class "Default")
      (node (ref "C4") (pin "1") (pinfunction "1_1") (pintype "passive"))
      (node (ref "U1") (pin "J3") (pinfunction "VBGR_J3") (pintype "passive"))
    )
    (net (code "23") (name "Net-(U1B-VCPFR)") (class "Default")
      (node (ref "C2") (pin "1") (pinfunction "1_1") (pintype "passive"))
      (node (ref "U1") (pin "F1") (pinfunction "VCPFR_F1") (pintype "passive"))
      (node (ref "U1") (pin "G3") (pinfunction "VCPST_G3") (pintype "passive"))
    )
    (net (code "24") (name "Net-(U1B-VLOADLM)") (class "Default")
      (node (ref "C5") (pin "1") (pinfunction "1_1") (pintype "passive"))
      (node (ref "U1") (pin "E3") (pinfunction "VLOADLM_E3") (pintype "passive"))
    )
    (net (code "25") (name "Net-(U1B-VRLFR)") (class "Default")
      (node (ref "C3") (pin "1") (pinfunction "1_1") (pintype "passive"))
      (node (ref "U1") (pin "C1") (pinfunction "VRLST_C1") (pintype "passive"))
      (node (ref "U1") (pin "C2") (pinfunction "VRLFR_C2") (pintype "passive"))
    )
    (net (code "26") (name "Net-(U1B-XCE)") (class "Default")
      (node (ref "R10") (pin "1") (pinfunction "1_1") (pintype "passive"))
      (node (ref "U1") (pin "A5") (pinfunction "XCE_A5") (pintype "input"))
    )
    (net (code "27") (name "Net-(U1B-XMASTER)") (class "Default")
      (node (ref "R14") (pin "1") (pinfunction "1_1") (pintype "passive"))
      (node (ref "U1") (pin "B5") (pinfunction "XMASTER_B5") (pintype "input"))
    )
    (net (code "28") (name "Net-(Y1-OUT)") (class "Default")
      (node (ref "R9") (pin "1") (pinfunction "1_1") (pintype "passive"))
      (node (ref "Y1") (pin "3") (pinfunction "OUT_3") (pintype "output"))
    )
    (net (code "29") (name "unconnected-(U1A-DLCKM-PadG13)") (class "Default")
      (node (ref "U1") (pin "G13") (pinfunction "DLCKM_G13") (pintype "bidirectional+no_connect"))
    )
    (net (code "30") (name "unconnected-(U1A-DLCKP-PadF13)") (class "Default")
      (node (ref "U1") (pin "F13") (pinfunction "DLCKP_F13") (pintype "bidirectional+no_connect"))
    )
    (net (code "31") (name "unconnected-(U1A-DLOMA-PadD13)") (class "Default")
      (node (ref "U1") (pin "D13") (pinfunction "DLOMA_D13") (pintype "bidirectional+no_connect"))
    )
    (net (code "32") (name "unconnected-(U1A-DLOMB-PadE11)") (class "Default")
      (node (ref "U1") (pin "E11") (pinfunction "DLOMB_E11") (pintype "bidirectional+no_connect"))
    )
    (net (code "33") (name "unconnected-(U1A-DLOMC-PadE13)") (class "Default")
      (node (ref "U1") (pin "E13") (pinfunction "DLOMC_E13") (pintype "bidirectional+no_connect"))
    )
    (net (code "34") (name "unconnected-(U1A-DLOMD-PadF12)") (class "Default")
      (node (ref "U1") (pin "F12") (pinfunction "DLOMD_F12") (pintype "bidirectional+no_connect"))
    )
    (net (code "35") (name "unconnected-(U1A-DLOME-PadG12)") (class "Default")
      (node (ref "U1") (pin "G12") (pinfunction "DLOME_G12") (pintype "bidirectional+no_connect"))
    )
    (net (code "36") (name "unconnected-(U1A-DLOMF-PadH12)") (class "Default")
      (node (ref "U1") (pin "H12") (pinfunction "DLOMF_H12") (pintype "bidirectional+no_connect"))
    )
    (net (code "37") (name "unconnected-(U1A-DLOMG-PadJ13)") (class "Default")
      (node (ref "U1") (pin "J13") (pinfunction "DLOMG_J13") (pintype "bidirectional+no_connect"))
    )
    (net (code "38") (name "unconnected-(U1A-DLOMH-PadK13)") (class "Default")
      (node (ref "U1") (pin "K13") (pinfunction "DLOMH_K13") (pintype "bidirectional+no_connect"))
    )
    (net (code "39") (name "unconnected-(U1A-DLOPA-PadD12)") (class "Default")
      (node (ref "U1") (pin "D12") (pinfunction "DLOPA_D12") (pintype "bidirectional+no_connect"))
    )
    (net (code "40") (name "unconnected-(U1A-DLOPB-PadD11)") (class "Default")
      (node (ref "U1") (pin "D11") (pinfunction "DLOPB_D11") (pintype "bidirectional+no_connect"))
    )
    (net (code "41") (name "unconnected-(U1A-DLOPC-PadE12)") (class "Default")
      (node (ref "U1") (pin "E12") (pinfunction "DLOPC_E12") (pintype "bidirectional+no_connect"))
    )
    (net (code "42") (name "unconnected-(U1A-DLOPD-PadF11)") (class "Default")
      (node (ref "U1") (pin "F11") (pinfunction "DLOPD_F11") (pintype "bidirectional+no_connect"))
    )
    (net (code "43") (name "unconnected-(U1A-DLOPE-PadG11)") (class "Default")
      (node (ref "U1") (pin "G11") (pinfunction "DLOPE_G11") (pintype "bidirectional+no_connect"))
    )
    (net (code "44") (name "unconnected-(U1A-DLOPF-PadH11)") (class "Default")
      (node (ref "U1") (pin "H11") (pinfunction "DLOPF_H11") (pintype "bidirectional+no_connect"))
    )
    (net (code "45") (name "unconnected-(U1A-DLOPG-PadJ12)") (class "Default")
      (node (ref "U1") (pin "J12") (pinfunction "DLOPG_J12") (pintype "bidirectional+no_connect"))
    )
    (net (code "46") (name "unconnected-(U1A-DLOPH-PadK12)") (class "Default")
      (node (ref "U1") (pin "K12") (pinfunction "DLOPH_K12") (pintype "bidirectional+no_connect"))
    )
    (net (code "47") (name "unconnected-(U1B-NC-PadB4)") (class "Default")
      (node (ref "U1") (pin "B4") (pinfunction "NC_B4") (pintype "passive+no_connect"))
    )
    (net (code "48") (name "unconnected-(U1B-NC-PadE1)") (class "Default")
      (node (ref "U1") (pin "E1") (pinfunction "NC_E1") (pintype "passive+no_connect"))
    )
    (net (code "49") (name "unconnected-(U1B-NC-PadE2)") (class "Default")
      (node (ref "U1") (pin "E2") (pinfunction "NC_E2") (pintype "passive+no_connect"))
    )
    (net (code "50") (name "unconnected-(U1B-NC-PadE4)") (class "Default")
      (node (ref "U1") (pin "E4") (pinfunction "NC_E4") (pintype "passive+no_connect"))
    )
    (net (code "51") (name "unconnected-(U1B-NC-PadF4)") (class "Default")
      (node (ref "U1") (pin "F4") (pinfunction "NC_F4") (pintype "passive+no_connect"))
    )
    (net (code "52") (name "unconnected-(U1B-NC-PadH3)") (class "Default")
      (node (ref "U1") (pin "H3") (pinfunction "NC_H3") (pintype "passive+no_connect"))
    )
    (net (code "53") (name "unconnected-(U1B-SDO-PadA4)") (class "Default")
      (node (ref "U1") (pin "A4") (pinfunction "SDO_A4") (pintype "output+no_connect"))
    )
  )
)
